# Half_bridge_load.net
KiCad netlist of a schematic drawn in Altium Designer
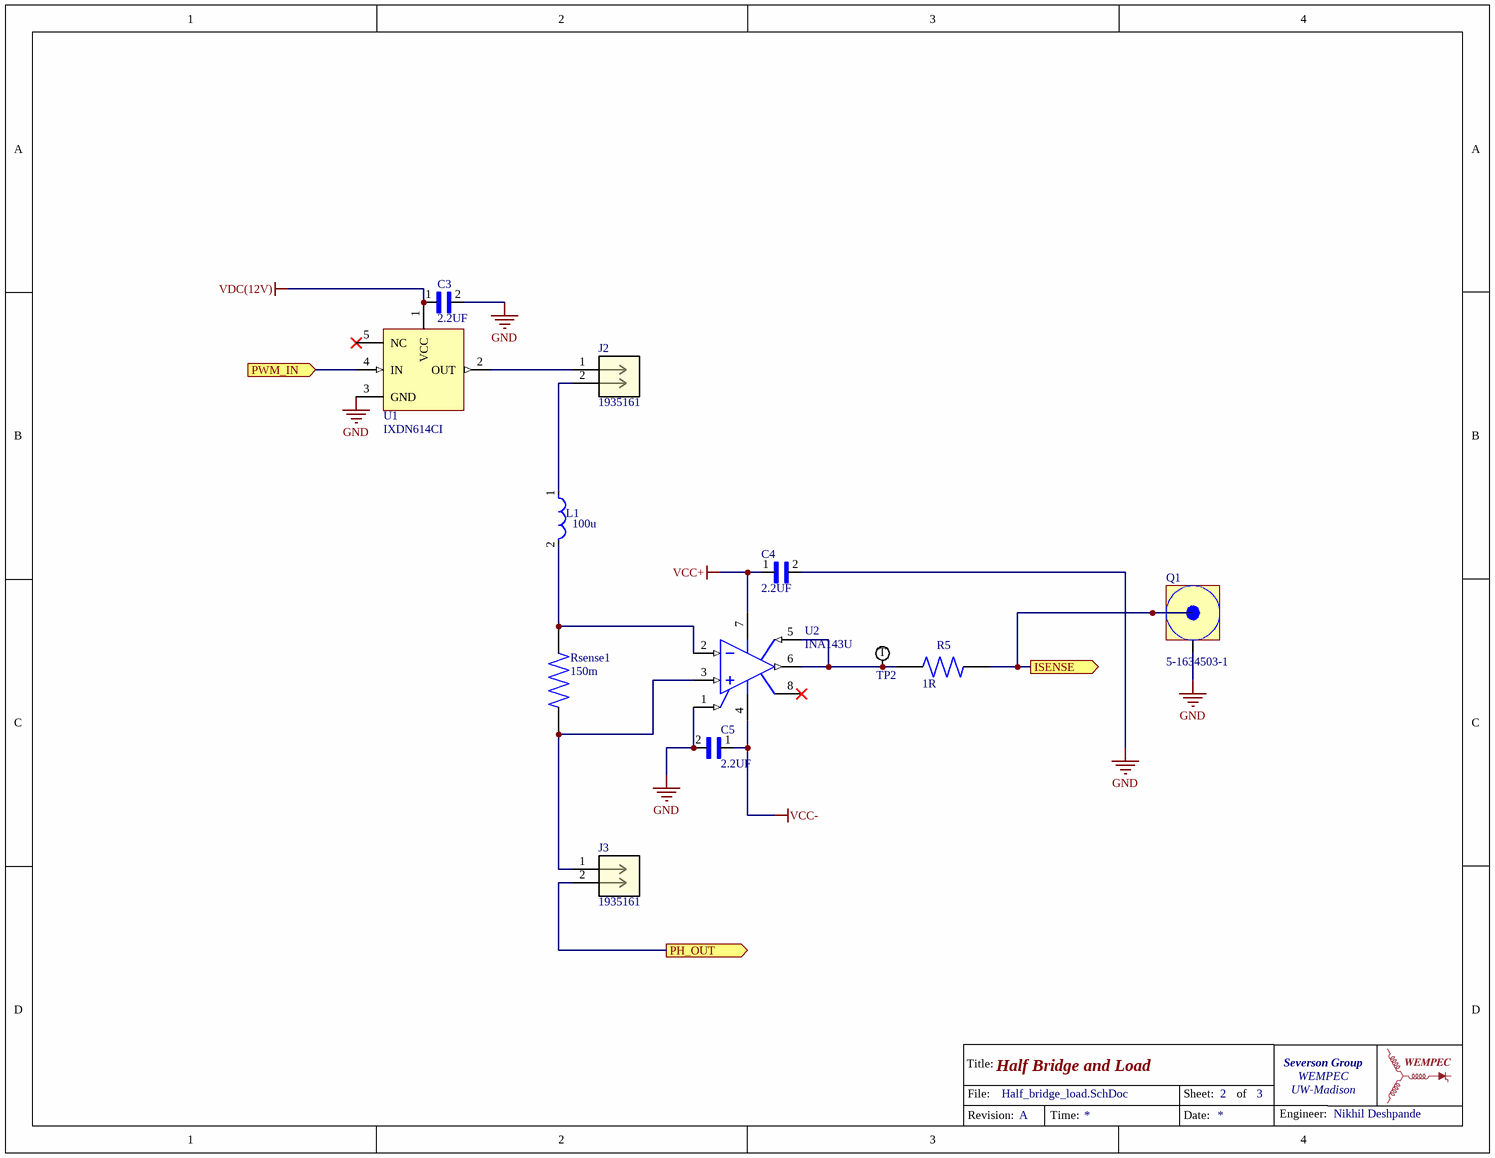
[diagram p0: Half_bridge_load.SchDoc]

(export (version "E")
  (design (tool "Eeschema 10.0.6"))
  (components
    (comp (ref "C3")
      (value "2.2UF")
      (footprint "0603_CAP")
      (description "CAP CER 2.2UF 35V X5R 0603")
      (fields
        (field (name "MANUFACTURER") "Murata")
        (field (name "MANUFACTURER PART NUMBER") "GRM188R6YA225MA12D")
      )
      (libsource (lib "Schlib_uInv01") (part "GRM188R6YA225MA12D"))
    )
    (comp (ref "C4")
      (value "2.2UF")
      (footprint "0603_CAP")
      (description "CAP CER 2.2UF 35V X5R 0603")
      (fields
        (field (name "MANUFACTURER") "Murata")
        (field (name "MANUFACTURER PART NUMBER") "GRM188R6YA225MA12D")
      )
      (libsource (lib "Schlib_uInv01") (part "GRM188R6YA225MA12D"))
    )
    (comp (ref "C5")
      (value "2.2UF")
      (footprint "0603_CAP")
      (description "CAP CER 2.2UF 35V X5R 0603")
      (fields
        (field (name "MANUFACTURER") "Murata")
        (field (name "MANUFACTURER PART NUMBER") "GRM188R6YA225MA12D")
      )
      (libsource (lib "") (part "GRM188R6YA225MA12D_1"))
    )
    (comp (ref "J2")
      (value "1935161")
      (footprint "PHOENIX_1935161")
      (description "Conn Terminal Blocks 2 POS 5mm Solder ST Thru-Hole 16A")
      (fields (field (name "MANUFACTURER") "Phoenix Contact") (field (name "VOLTAGE") "300V"))
      (libsource (lib "Schlib_uInv01") (part "1935161"))
    )
    (comp (ref "J3")
      (value "1935161")
      (footprint "PHOENIX_1935161")
      (description "Conn Terminal Blocks 2 POS 5mm Solder ST Thru-Hole 16A")
      (fields (field (name "MANUFACTURER") "Phoenix Contact") (field (name "VOLTAGE") "300V"))
      (libsource (lib "Schlib_uInv01") (part "1935161"))
    )
    (comp (ref "L1")
      (value "100u")
      (footprint "FP-PA4344_104NLT-MFG")
      (description "FIXED IND 100UH 5.3A 118 MOHM")
      (fields (field (name "MANUFACTURER") "Pulse") (field (name "MANUFACTURER PART NUMBER") "PA4344.104NLT"))
      (libsource (lib "Schlib_uInv01") (part "PA4344.104NLT"))
    )
    (comp (ref "Q1")
      (value "5-1634503-1")
      (footprint "5-1634503-1")
      (description "CONN BNC JACK STR 50 OHM PCB")
      (libsource (lib "Schlib_uInv01") (part "5-1634503-1"))
    )
    (comp (ref "R5")
      (value "1R")
      (footprint "0603_RES")
      (description "RES SMD 1 OHM 1% 1/10W 0603")
      (fields
        (field (name "MANUFACTURER") "Vishay Dale")
        (field (name "MANUFACTURER PART NUMBER") "RCG06031R00FKEA")
      )
      (libsource (lib "Schlib_uInv01") (part "RCG06031R00FKEA"))
    )
    (comp (ref "Rsense1")
      (value "150m")
      (footprint "RES_15_OHM")
      (description "Resistor; Wirewound; Res 0.15 Ohms; Pwr-Rtg 5 W; Tol 1%; Axial; Silicone; Cur-Sense")
      (fields (field (name "MANUFACTURER") "Ohmite") (field (name "MANUFACTURER PART NUMBER") "15FR150E"))
      (libsource (lib "Schlib_uInv01") (part "15FR150E"))
    )
    (comp (ref "TitleBlockWEMPEC2")
      (value "TitleBlockWEMPEC")
      (libsource (lib "Schlib_uInv01") (part "TitleBlockWEMPEC"))
    )
    (comp (ref "TP2")
      (value "Test Point")
      (footprint "TP_1.6MM")
      (description "Conn Test Point SKT 1 POS ST Thru-Hole 1 Port")
      (libsource (lib "Schlib_uInv01") (part "Test Point 36-5005ND"))
    )
    (comp (ref "U1")
      (value "IXDN614CI")
      (footprint "IXYS_TO-220-5_IXY")
      (description "14-Ampere Low-Side Ultrafast MOSFET Driver 5-Lead TO-220")
      (fields (field (name "MANUFACTURER") "IXYS"))
      (libsource (lib "Schlib_uInv01") (part "IXDN614CI"))
    )
    (comp (ref "U2")
      (value "INA143U")
      (footprint "SOIC127P599X175-8N")
      (description "SP Amp Difference Amplifier Single ±18V/36V 8-Pin SOIC Tube")
      (fields (field (name "MANUFACTURER") "Texas Instruments"))
      (libsource (lib "Schlib_uInv01") (part "INA143U"))
    )
  )
  (nets
    (net (code "1") (name "/ISENSE") (class "Default")
      (node (ref "Q1") (pin "1") (pinfunction "1_1") (pintype "passive"))
      (node (ref "R5") (pin "2") (pinfunction "2_2") (pintype "passive"))
    )
    (net (code "2") (name "/PH_OUT") (class "Default")
      (node (ref "J3") (pin "2") (pinfunction "2_2") (pintype "passive"))
    )
    (net (code "3") (name "/PWM_IN") (class "Default")
      (node (ref "U1") (pin "4") (pinfunction "IN_4") (pintype "input"))
    )
    (net (code "4") (name "GND") (class "Default")
      (node (ref "C3") (pin "2") (pinfunction "2_2") (pintype "passive"))
      (node (ref "C4") (pin "2") (pinfunction "2_2") (pintype "passive"))
      (node (ref "C5") (pin "2") (pinfunction "2_2") (pintype "passive"))
      (node (ref "Q1") (pin "2") (pinfunction "2_2") (pintype "passive"))
      (node (ref "U1") (pin "3") (pinfunction "GND_3") (pintype "power_in"))
      (node (ref "U2") (pin "1") (pinfunction "REF_1") (pintype "input"))
    )
    (net (code "5") (name "Net-(J2-Pad2)") (class "Default")
      (node (ref "J2") (pin "2") (pinfunction "2_2") (pintype "passive"))
      (node (ref "L1") (pin "1") (pinfunction "1_1") (pintype "passive"))
    )
    (net (code "6") (name "Net-(U1-OUT)") (class "Default")
      (node (ref "J2") (pin "1") (pinfunction "1_1") (pintype "passive"))
      (node (ref "U1") (pin "2") (pinfunction "OUT_2") (pintype "output"))
    )
    (net (code "7") (name "Net-(U2-IN+)") (class "Default")
      (node (ref "J3") (pin "1") (pinfunction "1_1") (pintype "passive"))
      (node (ref "Rsense1") (pin "2") (pinfunction "2_2") (pintype "passive"))
      (node (ref "U2") (pin "3") (pinfunction "IN+_3") (pintype "input"))
    )
    (net (code "8") (name "Net-(U2-IN-)") (class "Default")
      (node (ref "L1") (pin "2") (pinfunction "2_2") (pintype "passive"))
      (node (ref "Rsense1") (pin "1") (pinfunction "1_1") (pintype "passive"))
      (node (ref "U2") (pin "2") (pinfunction "IN-_2") (pintype "input"))
    )
    (net (code "9") (name "Net-(U2-OUTPUT)") (class "Default")
      (node (ref "R5") (pin "1") (pinfunction "1_1") (pintype "passive"))
      (node (ref "TP2") (pin "1") (pinfunction "1_1") (pintype "passive"))
      (node (ref "U2") (pin "5") (pinfunction "SENSE_5") (pintype "input"))
      (node (ref "U2") (pin "6") (pinfunction "OUTPUT_6") (pintype "output"))
    )
    (net (code "10") (name "VCC+") (class "Default")
      (node (ref "C4") (pin "1") (pinfunction "1_1") (pintype "passive"))
      (node (ref "U2") (pin "7") (pinfunction "V+_7") (pintype "power_in"))
    )
    (net (code "11") (name "VCC-") (class "Default")
      (node (ref "C5") (pin "1") (pinfunction "1_1") (pintype "passive"))
      (node (ref "U2") (pin "4") (pinfunction "V-_4") (pintype "power_in"))
    )
    (net (code "12") (name "VDC(12V)") (class "Default")
      (node (ref "C3") (pin "1") (pinfunction "1_1") (pintype "passive"))
      (node (ref "U1") (pin "1") (pinfunction "VCC_1") (pintype "power_in"))
    )
    (net (code "13") (name "unconnected-(U1-NC-Pad5)") (class "Default")
      (node (ref "U1") (pin "5") (pinfunction "NC_5") (pintype "passive+no_connect"))
    )
    (net (code "14") (name "unconnected-(U2-NC-Pad8)") (class "Default")
      (node (ref "U2") (pin "8") (pinfunction "NC_8") (pintype "passive+no_connect"))
    )
  )
)
